# LCD_ControlRev1.net
KiCad netlist of a schematic drawn in EAGLE
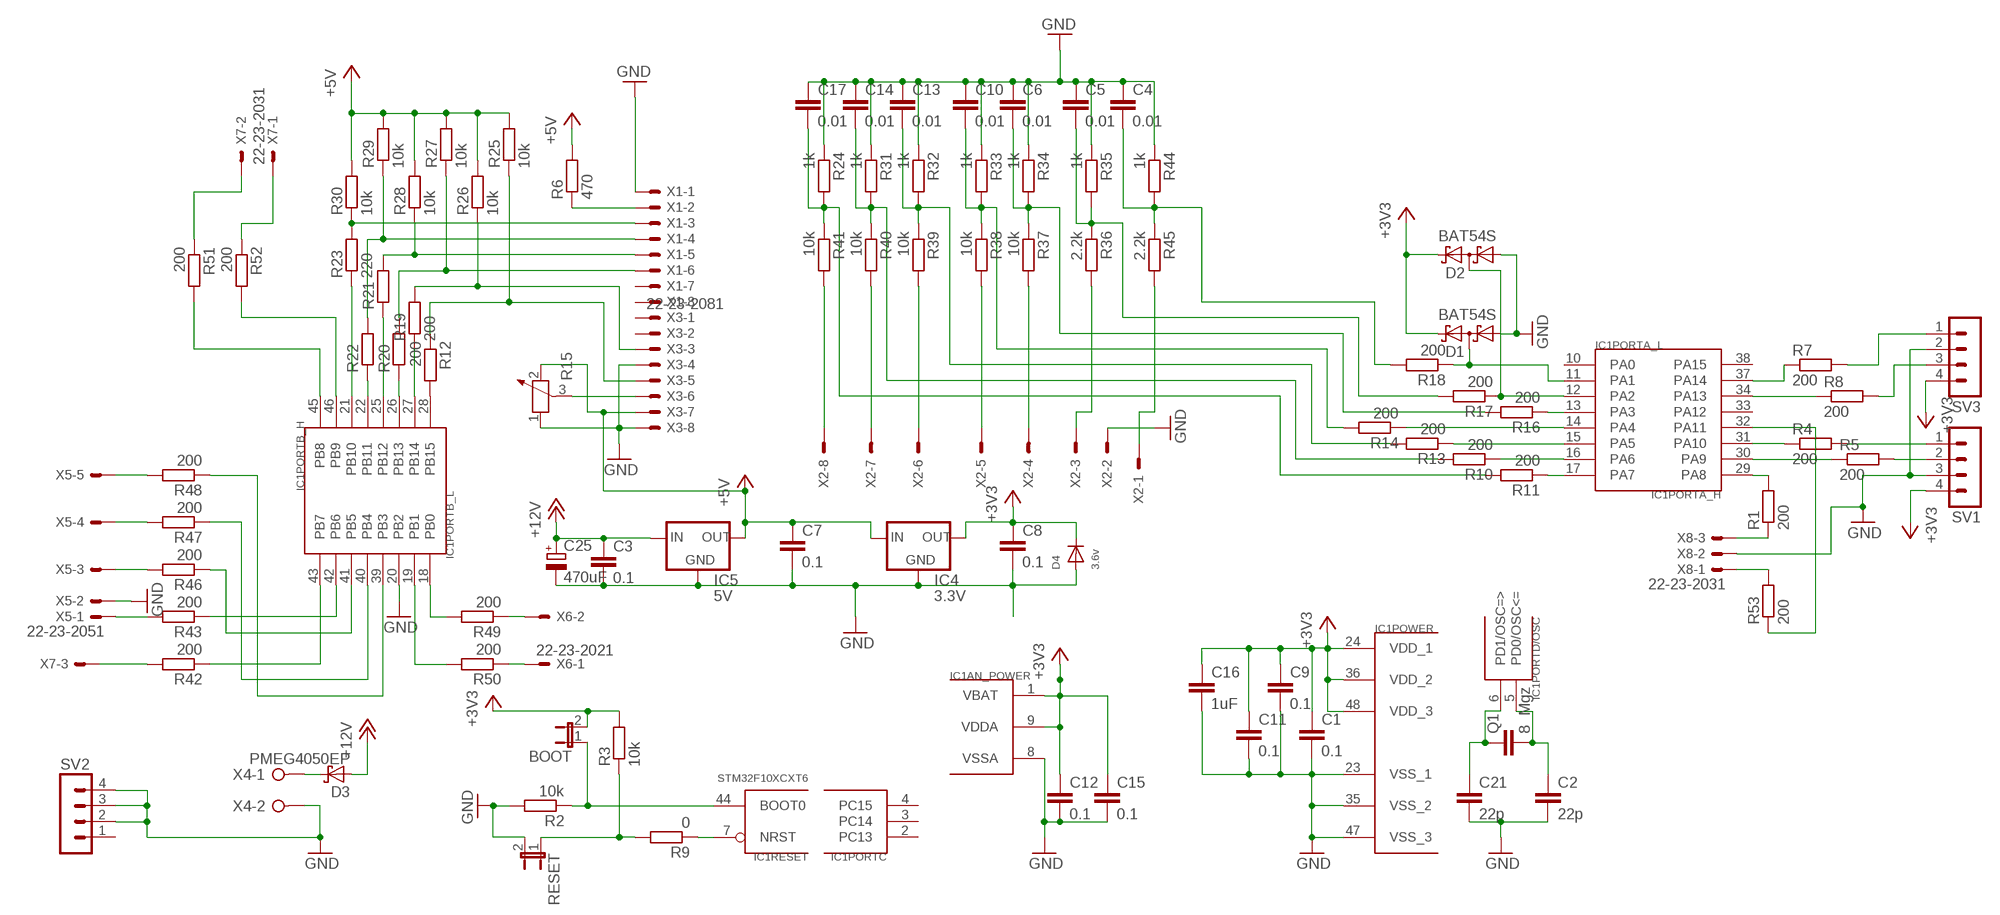
[diagram p0: schematic, sheet 1]

(export (version "E")
  (design (tool "Eeschema 10.0.6"))
  (components
    (comp (ref "BOOT")
      (value "JP1E")
      (footprint "eagle-import:JP1")
      (libsource (lib "eagle-import") (part "JP1E"))
    )
    (comp (ref "C1")
      (value "0.1")
      (footprint "eagle-import:C0402")
      (libsource (lib "eagle-import") (part "C-EUC0402"))
    )
    (comp (ref "C2")
      (value "22p")
      (footprint "eagle-import:C0603")
      (libsource (lib "eagle-import") (part "C-EUC0603"))
    )
    (comp (ref "C3")
      (value "0.1")
      (footprint "eagle-import:C1206")
      (libsource (lib "eagle-import") (part "C-EUC1206"))
    )
    (comp (ref "C4")
      (value "0.01")
      (footprint "eagle-import:C0603")
      (libsource (lib "eagle-import") (part "rcl_334_C-EUC0603"))
    )
    (comp (ref "C5")
      (value "0.01")
      (footprint "eagle-import:C0603")
      (libsource (lib "eagle-import") (part "rcl_334_C-EUC0603"))
    )
    (comp (ref "C6")
      (value "0.01")
      (footprint "eagle-import:C0603")
      (libsource (lib "eagle-import") (part "rcl_334_C-EUC0603"))
    )
    (comp (ref "C7")
      (value "0.1")
      (footprint "eagle-import:C1206")
      (libsource (lib "eagle-import") (part "C-EUC1206"))
    )
    (comp (ref "C8")
      (value "0.1")
      (footprint "eagle-import:C1206")
      (libsource (lib "eagle-import") (part "C-EUC1206"))
    )
    (comp (ref "C9")
      (value "0.1")
      (footprint "eagle-import:C0402")
      (libsource (lib "eagle-import") (part "C-EUC0402"))
    )
    (comp (ref "C10")
      (value "0.01")
      (footprint "eagle-import:C0603")
      (libsource (lib "eagle-import") (part "rcl_334_C-EUC0603"))
    )
    (comp (ref "C11")
      (value "0.1")
      (footprint "eagle-import:C0402")
      (libsource (lib "eagle-import") (part "C-EUC0402"))
    )
    (comp (ref "C12")
      (value "0.1")
      (footprint "eagle-import:C0402")
      (libsource (lib "eagle-import") (part "C-EUC0402"))
    )
    (comp (ref "C13")
      (value "0.01")
      (footprint "eagle-import:C0603")
      (libsource (lib "eagle-import") (part "rcl_334_C-EUC0603"))
    )
    (comp (ref "C14")
      (value "0.01")
      (footprint "eagle-import:C0603")
      (libsource (lib "eagle-import") (part "rcl_334_C-EUC0603"))
    )
    (comp (ref "C15")
      (value "0.1")
      (footprint "eagle-import:C0402")
      (libsource (lib "eagle-import") (part "C-EUC0402"))
    )
    (comp (ref "C16")
      (value "1uF")
      (footprint "eagle-import:C0603")
      (libsource (lib "eagle-import") (part "C-EUC0603"))
    )
    (comp (ref "C17")
      (value "0.01")
      (footprint "eagle-import:C0603")
      (libsource (lib "eagle-import") (part "rcl_334_C-EUC0603"))
    )
    (comp (ref "C21")
      (value "22p")
      (footprint "eagle-import:C0603")
      (libsource (lib "eagle-import") (part "C-EUC0603"))
    )
    (comp (ref "C25")
      (value "470uF")
      (footprint "eagle-import:E5-10,5")
      (libsource (lib "eagle-import") (part "CPOL-EUE5-10.5"))
    )
    (comp (ref "D1")
      (value "BAT54S")
      (footprint "eagle-import:SOT23")
      (libsource (lib "eagle-import") (part "BAT54S"))
    )
    (comp (ref "D2")
      (value "BAT54S")
      (footprint "eagle-import:SOT23")
      (libsource (lib "eagle-import") (part "BAT54S"))
    )
    (comp (ref "D3")
      (value "PMEG4050EP")
      (footprint "eagle-import:SOD128")
      (libsource (lib "eagle-import") (part "PMEG4050EP"))
    )
    (comp (ref "D4")
      (value "3.6v")
      (footprint "eagle-import:SOD-123")
      (libsource (lib "eagle-import") (part "DIODESOD-123"))
    )
    (comp (ref "IC1")
      (value "STM32F10XCXT6")
      (footprint "eagle-import:TQFP48")
      (libsource (lib "eagle-import") (part "STM32F10XCXT6"))
    )
    (comp (ref "IC4")
      (value "3.3V")
      (footprint "eagle-import:SOT223")
      (libsource (lib "eagle-import") (part "LM1117"))
    )
    (comp (ref "IC5")
      (value "5V")
      (footprint "eagle-import:SOT223")
      (libsource (lib "eagle-import") (part "LM1117"))
    )
    (comp (ref "Q1")
      (value "8 Mgz")
      (footprint "eagle-import:C050-024X044")
      (libsource (lib "eagle-import") (part "C-EU050-024X044"))
    )
    (comp (ref "R1")
      (value "200")
      (footprint "eagle-import:R0603")
      (libsource (lib "eagle-import") (part "R-EU_R0603"))
    )
    (comp (ref "R2")
      (value "10k")
      (footprint "eagle-import:R0603")
      (libsource (lib "eagle-import") (part "R-EU_R0603"))
    )
    (comp (ref "R3")
      (value "10k")
      (footprint "eagle-import:M1206")
      (libsource (lib "eagle-import") (part "R-EU_M1206"))
    )
    (comp (ref "R4")
      (value "200")
      (footprint "eagle-import:R0603")
      (libsource (lib "eagle-import") (part "R-EU_R0603"))
    )
    (comp (ref "R5")
      (value "200")
      (footprint "eagle-import:R0603")
      (libsource (lib "eagle-import") (part "R-EU_R0603"))
    )
    (comp (ref "R6")
      (value "470")
      (footprint "eagle-import:R0603")
      (libsource (lib "eagle-import") (part "R-EU_R0603"))
    )
    (comp (ref "R7")
      (value "200")
      (footprint "eagle-import:R0603")
      (libsource (lib "eagle-import") (part "R-EU_R0603"))
    )
    (comp (ref "R8")
      (value "200")
      (footprint "eagle-import:R0603")
      (libsource (lib "eagle-import") (part "R-EU_R0603"))
    )
    (comp (ref "R9")
      (value "0")
      (footprint "eagle-import:M1206")
      (libsource (lib "eagle-import") (part "R-EU_M1206"))
    )
    (comp (ref "R10")
      (value "200")
      (footprint "eagle-import:R0603")
      (libsource (lib "eagle-import") (part "R-EU_R0603"))
    )
    (comp (ref "R11")
      (value "200")
      (footprint "eagle-import:R0603")
      (libsource (lib "eagle-import") (part "R-EU_R0603"))
    )
    (comp (ref "R12")
      (value "200")
      (footprint "eagle-import:M1206")
      (libsource (lib "eagle-import") (part "R-EU_M1206"))
    )
    (comp (ref "R13")
      (value "200")
      (footprint "eagle-import:R0603")
      (libsource (lib "eagle-import") (part "R-EU_R0603"))
    )
    (comp (ref "R14")
      (value "200")
      (footprint "eagle-import:R0603")
      (libsource (lib "eagle-import") (part "R-EU_R0603"))
    )
    (comp (ref "R15")
      (value "POTENTIOMETER_PT-10S")
      (footprint "eagle-import:PT-10S")
      (libsource (lib "eagle-import") (part "POTENTIOMETER_PT-10S"))
    )
    (comp (ref "R16")
      (value "200")
      (footprint "eagle-import:R0603")
      (libsource (lib "eagle-import") (part "R-EU_R0603"))
    )
    (comp (ref "R17")
      (value "200")
      (footprint "eagle-import:R0603")
      (libsource (lib "eagle-import") (part "R-EU_R0603"))
    )
    (comp (ref "R18")
      (value "200")
      (footprint "eagle-import:R0603")
      (libsource (lib "eagle-import") (part "R-EU_R0603"))
    )
    (comp (ref "R19")
      (value "200")
      (footprint "eagle-import:R0603")
      (libsource (lib "eagle-import") (part "R-EU_R0603"))
    )
    (comp (ref "R20")
      (value "R-EU_R0603")
      (footprint "eagle-import:R0603")
      (libsource (lib "eagle-import") (part "R-EU_R0603"))
    )
    (comp (ref "R21")
      (value "R-EU_R0603")
      (footprint "eagle-import:R0603")
      (libsource (lib "eagle-import") (part "R-EU_R0603"))
    )
    (comp (ref "R22")
      (value "R-EU_R0603")
      (footprint "eagle-import:R0603")
      (libsource (lib "eagle-import") (part "R-EU_R0603"))
    )
    (comp (ref "R23")
      (value "220")
      (footprint "eagle-import:R0603")
      (libsource (lib "eagle-import") (part "R-EU_R0603"))
    )
    (comp (ref "R24")
      (value "1k")
      (footprint "eagle-import:R0603")
      (libsource (lib "eagle-import") (part "R-EU_R0603"))
    )
    (comp (ref "R25")
      (value "10k")
      (footprint "eagle-import:R0603")
      (libsource (lib "eagle-import") (part "R-EU_R0603"))
    )
    (comp (ref "R26")
      (value "10k")
      (footprint "eagle-import:R0603")
      (libsource (lib "eagle-import") (part "R-EU_R0603"))
    )
    (comp (ref "R27")
      (value "10k")
      (footprint "eagle-import:R0603")
      (libsource (lib "eagle-import") (part "R-EU_R0603"))
    )
    (comp (ref "R28")
      (value "10k")
      (footprint "eagle-import:R0603")
      (libsource (lib "eagle-import") (part "R-EU_R0603"))
    )
    (comp (ref "R29")
      (value "10k")
      (footprint "eagle-import:R0603")
      (libsource (lib "eagle-import") (part "R-EU_R0603"))
    )
    (comp (ref "R30")
      (value "10k")
      (footprint "eagle-import:R0603")
      (libsource (lib "eagle-import") (part "R-EU_R0603"))
    )
    (comp (ref "R31")
      (value "1k")
      (footprint "eagle-import:R0603")
      (libsource (lib "eagle-import") (part "R-EU_R0603"))
    )
    (comp (ref "R32")
      (value "1k")
      (footprint "eagle-import:R0603")
      (libsource (lib "eagle-import") (part "R-EU_R0603"))
    )
    (comp (ref "R33")
      (value "1k")
      (footprint "eagle-import:R0603")
      (libsource (lib "eagle-import") (part "R-EU_R0603"))
    )
    (comp (ref "R34")
      (value "1k")
      (footprint "eagle-import:R0603")
      (libsource (lib "eagle-import") (part "R-EU_R0603"))
    )
    (comp (ref "R35")
      (value "1k")
      (footprint "eagle-import:R0603")
      (fields (field (name "SPICEPREFIX") "R"))
      (libsource (lib "eagle-import") (part "R-EU_R0603"))
    )
    (comp (ref "R36")
      (value "2.2k")
      (footprint "eagle-import:R0603")
      (libsource (lib "eagle-import") (part "R-EU_R0603"))
    )
    (comp (ref "R37")
      (value "10k")
      (footprint "eagle-import:R0603")
      (libsource (lib "eagle-import") (part "R-EU_R0603"))
    )
    (comp (ref "R38")
      (value "10k")
      (footprint "eagle-import:R0603")
      (libsource (lib "eagle-import") (part "R-EU_R0603"))
    )
    (comp (ref "R39")
      (value "10k")
      (footprint "eagle-import:R0603")
      (libsource (lib "eagle-import") (part "R-EU_R0603"))
    )
    (comp (ref "R40")
      (value "10k")
      (footprint "eagle-import:R0603")
      (libsource (lib "eagle-import") (part "R-EU_R0603"))
    )
    (comp (ref "R41")
      (value "10k")
      (footprint "eagle-import:R0603")
      (libsource (lib "eagle-import") (part "R-EU_R0603"))
    )
    (comp (ref "R42")
      (value "200")
      (footprint "eagle-import:R0603")
      (libsource (lib "eagle-import") (part "R-EU_R0603"))
    )
    (comp (ref "R43")
      (value "200")
      (footprint "eagle-import:R0603")
      (libsource (lib "eagle-import") (part "R-EU_R0603"))
    )
    (comp (ref "R44")
      (value "1k")
      (footprint "eagle-import:R0603")
      (libsource (lib "eagle-import") (part "R-EU_R0603"))
    )
    (comp (ref "R45")
      (value "2.2k")
      (footprint "eagle-import:R0603")
      (libsource (lib "eagle-import") (part "R-EU_R0603"))
    )
    (comp (ref "R46")
      (value "200")
      (footprint "eagle-import:R0603")
      (libsource (lib "eagle-import") (part "R-EU_R0603"))
    )
    (comp (ref "R47")
      (value "200")
      (footprint "eagle-import:R0603")
      (libsource (lib "eagle-import") (part "R-EU_R0603"))
    )
    (comp (ref "R48")
      (value "200")
      (footprint "eagle-import:R0603")
      (libsource (lib "eagle-import") (part "R-EU_R0603"))
    )
    (comp (ref "R49")
      (value "200")
      (footprint "eagle-import:R0603")
      (libsource (lib "eagle-import") (part "R-EU_R0603"))
    )
    (comp (ref "R50")
      (value "200")
      (footprint "eagle-import:R0603")
      (libsource (lib "eagle-import") (part "R-EU_R0603"))
    )
    (comp (ref "R51")
      (value "200")
      (footprint "eagle-import:R0603")
      (libsource (lib "eagle-import") (part "R-EU_R0603"))
    )
    (comp (ref "R52")
      (value "200")
      (footprint "eagle-import:R0603")
      (libsource (lib "eagle-import") (part "R-EU_R0603"))
    )
    (comp (ref "R53")
      (value "200")
      (footprint "eagle-import:R0603")
      (libsource (lib "eagle-import") (part "R-EU_R0603"))
    )
    (comp (ref "RESET")
      (value "JP1E")
      (footprint "eagle-import:JP1")
      (libsource (lib "eagle-import") (part "JP1E"))
    )
    (comp (ref "SV1")
      (value "MA04-1")
      (footprint "eagle-import:MA04-1")
      (libsource (lib "eagle-import") (part "MA04-1"))
    )
    (comp (ref "SV2")
      (value "MA04-1")
      (footprint "eagle-import:MA04-1")
      (libsource (lib "eagle-import") (part "MA04-1"))
    )
    (comp (ref "SV3")
      (value "MA04-1")
      (footprint "eagle-import:MA04-1")
      (libsource (lib "eagle-import") (part "MA04-1"))
    )
    (comp (ref "X1")
      (value "22-23-2081")
      (footprint "eagle-import:22-23-2081")
      (fields (field (name "MF") "MOLEX"))
      (libsource (lib "eagle-import") (part "22-23-2081"))
    )
    (comp (ref "X2")
      (value "22-23-2081")
      (footprint "eagle-import:22-23-2081")
      (fields (field (name "MF") "MOLEX"))
      (libsource (lib "eagle-import") (part "con-molex_165_22-23-2081"))
    )
    (comp (ref "X3")
      (value "22-23-2081")
      (footprint "eagle-import:22-23-2081")
      (fields (field (name "MF") "MOLEX"))
      (libsource (lib "eagle-import") (part "22-23-2081"))
    )
    (comp (ref "X4")
      (value "W237-02P")
      (footprint "eagle-import:W237-132")
      (libsource (lib "eagle-import") (part "W237-02P"))
    )
    (comp (ref "X5")
      (value "22-23-2051")
      (footprint "eagle-import:22-23-2051")
      (fields (field (name "MF") "MOLEX"))
      (libsource (lib "eagle-import") (part "22-23-2051"))
    )
    (comp (ref "X6")
      (value "22-23-2021")
      (footprint "eagle-import:22-23-2021")
      (fields (field (name "MF") "MOLEX"))
      (libsource (lib "eagle-import") (part "22-23-2021"))
    )
    (comp (ref "X7")
      (value "22-23-2031")
      (footprint "eagle-import:22-23-2031")
      (fields (field (name "MF") "MOLEX"))
      (libsource (lib "eagle-import") (part "22-23-2031"))
    )
    (comp (ref "X8")
      (value "22-23-2031")
      (footprint "eagle-import:22-23-2031")
      (fields (field (name "MF") "MOLEX"))
      (libsource (lib "eagle-import") (part "22-23-2031"))
    )
  )
  (nets
    (net (code "1") (name "+3V3") (class "Default")
      (node (ref "BOOT") (pin "2") (pinfunction "2_2") (pintype "passive"))
      (node (ref "C1") (pin "1") (pinfunction "1_1") (pintype "passive"))
      (node (ref "C11") (pin "1") (pinfunction "1_1") (pintype "passive"))
      (node (ref "C12") (pin "1") (pinfunction "1_1") (pintype "passive"))
      (node (ref "C15") (pin "1") (pinfunction "1_1") (pintype "passive"))
      (node (ref "C16") (pin "1") (pinfunction "1_1") (pintype "passive"))
      (node (ref "C8") (pin "1") (pinfunction "1_1") (pintype "passive"))
      (node (ref "C9") (pin "1") (pinfunction "1_1") (pintype "passive"))
      (node (ref "D1") (pin "2") (pinfunction "C2_2") (pintype "passive"))
      (node (ref "D2") (pin "2") (pinfunction "C2_2") (pintype "passive"))
      (node (ref "D4") (pin "C") (pinfunction "C_C") (pintype "passive"))
      (node (ref "IC1") (pin "1") (pinfunction "VBAT_1") (pintype "power_in"))
      (node (ref "IC1") (pin "24") (pinfunction "VDD_1_24") (pintype "power_in"))
      (node (ref "IC1") (pin "36") (pinfunction "VDD_2_36") (pintype "power_in"))
      (node (ref "IC1") (pin "48") (pinfunction "VDD_3_48") (pintype "power_in"))
      (node (ref "IC1") (pin "9") (pinfunction "VDDA_9") (pintype "power_in"))
      (node (ref "IC4") (pin "2") (pinfunction "OUT_2") (pintype "passive"))
      (node (ref "IC4") (pin "4") (pinfunction "OUT_4") (pintype "passive"))
      (node (ref "R3") (pin "2") (pinfunction "2_2") (pintype "passive"))
      (node (ref "SV1") (pin "4") (pinfunction "4_4") (pintype "passive"))
      (node (ref "SV3") (pin "4") (pinfunction "4_4") (pintype "passive"))
    )
    (net (code "2") (name "+5V") (class "Default")
      (node (ref "C7") (pin "1") (pinfunction "1_1") (pintype "passive"))
      (node (ref "IC4") (pin "3") (pinfunction "IN_3") (pintype "input"))
      (node (ref "IC5") (pin "2") (pinfunction "OUT_2") (pintype "passive"))
      (node (ref "IC5") (pin "4") (pinfunction "OUT_4") (pintype "passive"))
      (node (ref "R15") (pin "2") (pinfunction "2_2") (pintype "passive"))
      (node (ref "R25") (pin "2") (pinfunction "2_2") (pintype "passive"))
      (node (ref "R26") (pin "2") (pinfunction "2_2") (pintype "passive"))
      (node (ref "R27") (pin "2") (pinfunction "2_2") (pintype "passive"))
      (node (ref "R28") (pin "2") (pinfunction "2_2") (pintype "passive"))
      (node (ref "R29") (pin "2") (pinfunction "2_2") (pintype "passive"))
      (node (ref "R30") (pin "2") (pinfunction "2_2") (pintype "passive"))
      (node (ref "R6") (pin "2") (pinfunction "2_2") (pintype "passive"))
      (node (ref "X3") (pin "7") (pinfunction "S_7") (pintype "passive"))
    )
    (net (code "3") (name "+12V") (class "Default")
      (node (ref "C25") (pin "+") (pinfunction "+_+") (pintype "passive"))
      (node (ref "C3") (pin "1") (pinfunction "1_1") (pintype "passive"))
      (node (ref "D3") (pin "2") (pinfunction "A_2") (pintype "passive"))
      (node (ref "IC5") (pin "3") (pinfunction "IN_3") (pintype "input"))
    )
    (net (code "4") (name "GND") (class "Default")
      (node (ref "C1") (pin "2") (pinfunction "2_2") (pintype "passive"))
      (node (ref "C10") (pin "1") (pinfunction "1_1") (pintype "passive"))
      (node (ref "C11") (pin "2") (pinfunction "2_2") (pintype "passive"))
      (node (ref "C12") (pin "2") (pinfunction "2_2") (pintype "passive"))
      (node (ref "C13") (pin "1") (pinfunction "1_1") (pintype "passive"))
      (node (ref "C14") (pin "1") (pinfunction "1_1") (pintype "passive"))
      (node (ref "C15") (pin "2") (pinfunction "2_2") (pintype "passive"))
      (node (ref "C16") (pin "2") (pinfunction "2_2") (pintype "passive"))
      (node (ref "C17") (pin "1") (pinfunction "1_1") (pintype "passive"))
      (node (ref "C2") (pin "2") (pinfunction "2_2") (pintype "passive"))
      (node (ref "C21") (pin "2") (pinfunction "2_2") (pintype "passive"))
      (node (ref "C25") (pin "-") (pinfunction "-_-") (pintype "passive"))
      (node (ref "C3") (pin "2") (pinfunction "2_2") (pintype "passive"))
      (node (ref "C4") (pin "1") (pinfunction "1_1") (pintype "passive"))
      (node (ref "C5") (pin "1") (pinfunction "1_1") (pintype "passive"))
      (node (ref "C6") (pin "1") (pinfunction "1_1") (pintype "passive"))
      (node (ref "C7") (pin "2") (pinfunction "2_2") (pintype "passive"))
      (node (ref "C8") (pin "2") (pinfunction "2_2") (pintype "passive"))
      (node (ref "C9") (pin "2") (pinfunction "2_2") (pintype "passive"))
      (node (ref "D1") (pin "1") (pinfunction "A1_1") (pintype "passive"))
      (node (ref "D2") (pin "1") (pinfunction "A1_1") (pintype "passive"))
      (node (ref "D4") (pin "A") (pinfunction "A_A") (pintype "passive"))
      (node (ref "IC1") (pin "20") (pinfunction "PB2_20") (pintype "bidirectional"))
      (node (ref "IC1") (pin "23") (pinfunction "VSS_1_23") (pintype "power_in"))
      (node (ref "IC1") (pin "35") (pinfunction "VSS_2_35") (pintype "power_in"))
      (node (ref "IC1") (pin "47") (pinfunction "VSS_3_47") (pintype "power_in"))
      (node (ref "IC1") (pin "8") (pinfunction "VSSA_8") (pintype "power_in"))
      (node (ref "IC4") (pin "1") (pinfunction "GND_1") (pintype "input"))
      (node (ref "IC5") (pin "1") (pinfunction "GND_1") (pintype "input"))
      (node (ref "R15") (pin "1") (pinfunction "1_1") (pintype "passive"))
      (node (ref "R2") (pin "2") (pinfunction "2_2") (pintype "passive"))
      (node (ref "R24") (pin "1") (pinfunction "1_1") (pintype "passive"))
      (node (ref "R31") (pin "1") (pinfunction "1_1") (pintype "passive"))
      (node (ref "R32") (pin "1") (pinfunction "1_1") (pintype "passive"))
      (node (ref "R33") (pin "1") (pinfunction "1_1") (pintype "passive"))
      (node (ref "R34") (pin "1") (pinfunction "1_1") (pintype "passive"))
      (node (ref "R35") (pin "1") (pinfunction "1_1") (pintype "passive"))
      (node (ref "R44") (pin "1") (pinfunction "1_1") (pintype "passive"))
      (node (ref "RESET") (pin "2") (pinfunction "2_2") (pintype "passive"))
      (node (ref "SV1") (pin "3") (pinfunction "3_3") (pintype "passive"))
      (node (ref "SV2") (pin "2") (pinfunction "2_2") (pintype "passive"))
      (node (ref "SV2") (pin "3") (pinfunction "3_3") (pintype "passive"))
      (node (ref "SV2") (pin "4") (pinfunction "4_4") (pintype "passive"))
      (node (ref "SV3") (pin "2") (pinfunction "2_2") (pintype "passive"))
      (node (ref "X1") (pin "1") (pinfunction "S_1") (pintype "passive"))
      (node (ref "X2") (pin "2") (pinfunction "S_2") (pintype "passive"))
      (node (ref "X3") (pin "4") (pinfunction "S_4") (pintype "passive"))
      (node (ref "X3") (pin "8") (pinfunction "S_8") (pintype "passive"))
      (node (ref "X4") (pin "2") (pinfunction "KL_2") (pintype "passive"))
      (node (ref "X5") (pin "2") (pinfunction "S_2") (pintype "passive"))
      (node (ref "X8") (pin "2") (pinfunction "S_2") (pintype "passive"))
    )
    (net (code "5") (name "Net-(C4-Pad2)") (class "Default")
      (node (ref "C4") (pin "2") (pinfunction "2_2") (pintype "passive"))
      (node (ref "R18") (pin "2") (pinfunction "2_2") (pintype "passive"))
      (node (ref "R44") (pin "2") (pinfunction "2_2") (pintype "passive"))
      (node (ref "R45") (pin "1") (pinfunction "1_1") (pintype "passive"))
    )
    (net (code "6") (name "Net-(C5-Pad2)") (class "Default")
      (node (ref "C5") (pin "2") (pinfunction "2_2") (pintype "passive"))
      (node (ref "R17") (pin "2") (pinfunction "2_2") (pintype "passive"))
      (node (ref "R35") (pin "2") (pinfunction "2_2") (pintype "passive"))
      (node (ref "R36") (pin "1") (pinfunction "1_1") (pintype "passive"))
    )
    (net (code "7") (name "Net-(C6-Pad2)") (class "Default")
      (node (ref "C6") (pin "2") (pinfunction "2_2") (pintype "passive"))
      (node (ref "R16") (pin "2") (pinfunction "2_2") (pintype "passive"))
      (node (ref "R34") (pin "2") (pinfunction "2_2") (pintype "passive"))
      (node (ref "R37") (pin "1") (pinfunction "1_1") (pintype "passive"))
    )
    (net (code "8") (name "Net-(C10-Pad2)") (class "Default")
      (node (ref "C10") (pin "2") (pinfunction "2_2") (pintype "passive"))
      (node (ref "R14") (pin "2") (pinfunction "2_2") (pintype "passive"))
      (node (ref "R33") (pin "2") (pinfunction "2_2") (pintype "passive"))
      (node (ref "R38") (pin "1") (pinfunction "1_1") (pintype "passive"))
    )
    (net (code "9") (name "Net-(C13-Pad2)") (class "Default")
      (node (ref "C13") (pin "2") (pinfunction "2_2") (pintype "passive"))
      (node (ref "R13") (pin "2") (pinfunction "2_2") (pintype "passive"))
      (node (ref "R32") (pin "2") (pinfunction "2_2") (pintype "passive"))
      (node (ref "R39") (pin "1") (pinfunction "1_1") (pintype "passive"))
    )
    (net (code "10") (name "Net-(C14-Pad2)") (class "Default")
      (node (ref "C14") (pin "2") (pinfunction "2_2") (pintype "passive"))
      (node (ref "R10") (pin "2") (pinfunction "2_2") (pintype "passive"))
      (node (ref "R31") (pin "2") (pinfunction "2_2") (pintype "passive"))
      (node (ref "R40") (pin "1") (pinfunction "1_1") (pintype "passive"))
    )
    (net (code "11") (name "Net-(C17-Pad2)") (class "Default")
      (node (ref "C17") (pin "2") (pinfunction "2_2") (pintype "passive"))
      (node (ref "R11") (pin "2") (pinfunction "2_2") (pintype "passive"))
      (node (ref "R24") (pin "2") (pinfunction "2_2") (pintype "passive"))
      (node (ref "R41") (pin "1") (pinfunction "1_1") (pintype "passive"))
    )
    (net (code "12") (name "Net-(D1-C1A2)") (class "Default")
      (node (ref "D1") (pin "3") (pinfunction "C1A2_3") (pintype "passive"))
      (node (ref "IC1") (pin "11") (pinfunction "PA1_11") (pintype "bidirectional"))
      (node (ref "R18") (pin "1") (pinfunction "1_1") (pintype "passive"))
    )
    (net (code "13") (name "Net-(D2-C1A2)") (class "Default")
      (node (ref "D2") (pin "3") (pinfunction "C1A2_3") (pintype "passive"))
      (node (ref "IC1") (pin "12") (pinfunction "PA2_12") (pintype "bidirectional"))
      (node (ref "R17") (pin "1") (pinfunction "1_1") (pintype "passive"))
    )
    (net (code "14") (name "Net-(D3-K)") (class "Default")
      (node (ref "D3") (pin "1") (pinfunction "K_1") (pintype "passive"))
      (node (ref "X4") (pin "1") (pinfunction "KL_1") (pintype "passive"))
    )
    (net (code "15") (name "Net-(IC1B-PA8)") (class "Default")
      (node (ref "IC1") (pin "29") (pinfunction "PA8_29") (pintype "bidirectional"))
      (node (ref "R1") (pin "2") (pinfunction "2_2") (pintype "passive"))
    )
    (net (code "16") (name "Net-(IC1B-PA9)") (class "Default")
      (node (ref "IC1") (pin "30") (pinfunction "PA9_30") (pintype "bidirectional"))
      (node (ref "R5") (pin "1") (pinfunction "1_1") (pintype "passive"))
    )
    (net (code "17") (name "Net-(IC1B-PA10)") (class "Default")
      (node (ref "IC1") (pin "31") (pinfunction "PA10_31") (pintype "bidirectional"))
      (node (ref "R4") (pin "1") (pinfunction "1_1") (pintype "passive"))
    )
    (net (code "18") (name "Net-(IC1B-PA11)") (class "Default")
      (node (ref "IC1") (pin "32") (pinfunction "PA11_32") (pintype "bidirectional"))
      (node (ref "R53") (pin "1") (pinfunction "1_1") (pintype "passive"))
    )
    (net (code "19") (name "Net-(IC1B-PA13)") (class "Default")
      (node (ref "IC1") (pin "34") (pinfunction "PA13_34") (pintype "bidirectional"))
      (node (ref "R8") (pin "1") (pinfunction "1_1") (pintype "passive"))
    )
    (net (code "20") (name "Net-(IC1B-PA14)") (class "Default")
      (node (ref "IC1") (pin "37") (pinfunction "PA14_37") (pintype "bidirectional"))
      (node (ref "R7") (pin "1") (pinfunction "1_1") (pintype "passive"))
    )
    (net (code "21") (name "Net-(IC1C-PA3)") (class "Default")
      (node (ref "IC1") (pin "13") (pinfunction "PA3_13") (pintype "bidirectional"))
      (node (ref "R16") (pin "1") (pinfunction "1_1") (pintype "passive"))
    )
    (net (code "22") (name "Net-(IC1C-PA4)") (class "Default")
      (node (ref "IC1") (pin "14") (pinfunction "PA4_14") (pintype "bidirectional"))
      (node (ref "R14") (pin "1") (pinfunction "1_1") (pintype "passive"))
    )
    (net (code "23") (name "Net-(IC1C-PA5)") (class "Default")
      (node (ref "IC1") (pin "15") (pinfunction "PA5_15") (pintype "bidirectional"))
      (node (ref "R13") (pin "1") (pinfunction "1_1") (pintype "passive"))
    )
    (net (code "24") (name "Net-(IC1C-PA6)") (class "Default")
      (node (ref "IC1") (pin "16") (pinfunction "PA6_16") (pintype "bidirectional"))
      (node (ref "R10") (pin "1") (pinfunction "1_1") (pintype "passive"))
    )
    (net (code "25") (name "Net-(IC1C-PA7)") (class "Default")
      (node (ref "IC1") (pin "17") (pinfunction "PA7_17") (pintype "bidirectional"))
      (node (ref "R11") (pin "1") (pinfunction "1_1") (pintype "passive"))
    )
    (net (code "26") (name "Net-(IC1D-PB8)") (class "Default")
      (node (ref "IC1") (pin "45") (pinfunction "PB8_45") (pintype "bidirectional"))
      (node (ref "R51") (pin "2") (pinfunction "2_2") (pintype "passive"))
    )
    (net (code "27") (name "Net-(IC1D-PB9)") (class "Default")
      (node (ref "IC1") (pin "46") (pinfunction "PB9_46") (pintype "bidirectional"))
      (node (ref "R52") (pin "2") (pinfunction "2_2") (pintype "passive"))
    )
    (net (code "28") (name "Net-(IC1D-PB10)") (class "Default")
      (node (ref "IC1") (pin "21") (pinfunction "PB10_21") (pintype "bidirectional"))
      (node (ref "R23") (pin "1") (pinfunction "1_1") (pintype "passive"))
    )
    (net (code "29") (name "Net-(IC1D-PB11)") (class "Default")
      (node (ref "IC1") (pin "22") (pinfunction "PB11_22") (pintype "bidirectional"))
      (node (ref "R22") (pin "1") (pinfunction "1_1") (pintype "passive"))
    )
    (net (code "30") (name "Net-(IC1D-PB12)") (class "Default")
      (node (ref "IC1") (pin "25") (pinfunction "PB12_25") (pintype "bidirectional"))
      (node (ref "R21") (pin "1") (pinfunction "1_1") (pintype "passive"))
    )
    (net (code "31") (name "Net-(IC1D-PB13)") (class "Default")
      (node (ref "IC1") (pin "26") (pinfunction "PB13_26") (pintype "bidirectional"))
      (node (ref "R20") (pin "1") (pinfunction "1_1") (pintype "passive"))
    )
    (net (code "32") (name "Net-(IC1D-PB14)") (class "Default")
      (node (ref "IC1") (pin "27") (pinfunction "PB14_27") (pintype "bidirectional"))
      (node (ref "R19") (pin "1") (pinfunction "1_1") (pintype "passive"))
    )
    (net (code "33") (name "Net-(IC1D-PB15)") (class "Default")
      (node (ref "IC1") (pin "28") (pinfunction "PB15_28") (pintype "bidirectional"))
      (node (ref "R12") (pin "2") (pinfunction "2_2") (pintype "passive"))
    )
    (net (code "34") (name "Net-(IC1E-PB0)") (class "Default")
      (node (ref "IC1") (pin "18") (pinfunction "PB0_18") (pintype "bidirectional"))
      (node (ref "R49") (pin "2") (pinfunction "2_2") (pintype "passive"))
    )
    (net (code "35") (name "Net-(IC1E-PB1)") (class "Default")
      (node (ref "IC1") (pin "19") (pinfunction "PB1_19") (pintype "bidirectional"))
      (node (ref "R50") (pin "2") (pinfunction "2_2") (pintype "passive"))
    )
    (net (code "36") (name "Net-(IC1E-PB3)") (class "Default")
      (node (ref "IC1") (pin "39") (pinfunction "PB3_39") (pintype "bidirectional"))
      (node (ref "R48") (pin "1") (pinfunction "1_1") (pintype "passive"))
    )
    (net (code "37") (name "Net-(IC1E-PB4)") (class "Default")
      (node (ref "IC1") (pin "40") (pinfunction "PB4_40") (pintype "bidirectional"))
      (node (ref "R47") (pin "1") (pinfunction "1_1") (pintype "passive"))
    )
    (net (code "38") (name "Net-(IC1E-PB5)") (class "Default")
      (node (ref "IC1") (pin "41") (pinfunction "PB5_41") (pintype "bidirectional"))
      (node (ref "R46") (pin "1") (pinfunction "1_1") (pintype "passive"))
    )
    (net (code "39") (name "Net-(IC1E-PB6)") (class "Default")
      (node (ref "IC1") (pin "42") (pinfunction "PB6_42") (pintype "bidirectional"))
      (node (ref "R43") (pin "1") (pinfunction "1_1") (pintype "passive"))
    )
    (net (code "40") (name "Net-(IC1E-PB7)") (class "Default")
      (node (ref "IC1") (pin "43") (pinfunction "PB7_43") (pintype "bidirectional"))
      (node (ref "R42") (pin "1") (pinfunction "1_1") (pintype "passive"))
    )
    (net (code "41") (name "Net-(IC1G-PD0{slash}OSC<=)") (class "Default")
      (node (ref "C2") (pin "1") (pinfunction "1_1") (pintype "passive"))
      (node (ref "IC1") (pin "5") (pinfunction "PD0/OSC<=_5") (pintype "bidirectional"))
      (node (ref "Q1") (pin "2") (pinfunction "2_2") (pintype "passive"))
    )
    (net (code "42") (name "Net-(IC1G-PD1{slash}OSC=>)") (class "Default")
      (node (ref "C21") (pin "1") (pinfunction "1_1") (pintype "passive"))
      (node (ref "IC1") (pin "6") (pinfunction "PD1/OSC=>_6") (pintype "bidirectional"))
      (node (ref "Q1") (pin "1") (pinfunction "1_1") (pintype "passive"))
    )
    (net (code "43") (name "Net-(IC1I-BOOT0)") (class "Default")
      (node (ref "BOOT") (pin "1") (pinfunction "1_1") (pintype "passive"))
      (node (ref "IC1") (pin "44") (pinfunction "BOOT0_44") (pintype "input"))
      (node (ref "R2") (pin "1") (pinfunction "1_1") (pintype "passive"))
    )
    (net (code "44") (name "Net-(IC1I-NRST)") (class "Default")
      (node (ref "IC1") (pin "7") (pinfunction "NRST_7") (pintype "input"))
      (node (ref "R9") (pin "1") (pinfunction "1_1") (pintype "passive"))
    )
    (net (code "45") (name "Net-(R3-Pad1)") (class "Default")
      (node (ref "R3") (pin "1") (pinfunction "1_1") (pintype "passive"))
      (node (ref "R9") (pin "2") (pinfunction "2_2") (pintype "passive"))
      (node (ref "RESET") (pin "1") (pinfunction "1_1") (pintype "passive"))
    )
    (net (code "46") (name "Net-(R4-Pad2)") (class "Default")
      (node (ref "R4") (pin "2") (pinfunction "2_2") (pintype "passive"))
      (node (ref "SV1") (pin "1") (pinfunction "1_1") (pintype "passive"))
    )
    (net (code "47") (name "Net-(R5-Pad2)") (class "Default")
      (node (ref "R5") (pin "2") (pinfunction "2_2") (pintype "passive"))
      (node (ref "SV1") (pin "2") (pinfunction "2_2") (pintype "passive"))
    )
    (net (code "48") (name "Net-(R7-Pad2)") (class "Default")
      (node (ref "R7") (pin "2") (pinfunction "2_2") (pintype "passive"))
      (node (ref "SV3") (pin "1") (pinfunction "1_1") (pintype "passive"))
    )
    (net (code "49") (name "Net-(R8-Pad2)") (class "Default")
      (node (ref "R8") (pin "2") (pinfunction "2_2") (pintype "passive"))
      (node (ref "SV3") (pin "3") (pinfunction "3_3") (pintype "passive"))
    )
    (net (code "50") (name "Net-(X1B-S)") (class "Default")
      (node (ref "R6") (pin "1") (pinfunction "1_1") (pintype "passive"))
      (node (ref "X1") (pin "2") (pinfunction "S_2") (pintype "passive"))
    )
    (net (code "51") (name "Net-(X1C-S)") (class "Default")
      (node (ref "R23") (pin "2") (pinfunction "2_2") (pintype "passive"))
      (node (ref "R30") (pin "1") (pinfunction "1_1") (pintype "passive"))
      (node (ref "X1") (pin "3") (pinfunction "S_3") (pintype "passive"))
    )
    (net (code "52") (name "Net-(X1D-S)") (class "Default")
      (node (ref "R22") (pin "2") (pinfunction "2_2") (pintype "passive"))
      (node (ref "R29") (pin "1") (pinfunction "1_1") (pintype "passive"))
      (node (ref "X1") (pin "4") (pinfunction "S_4") (pintype "passive"))
    )
    (net (code "53") (name "Net-(X1E-S)") (class "Default")
      (node (ref "R21") (pin "2") (pinfunction "2_2") (pintype "passive"))
      (node (ref "R28") (pin "1") (pinfunction "1_1") (pintype "passive"))
      (node (ref "X1") (pin "5") (pinfunction "S_5") (pintype "passive"))
    )
    (net (code "54") (name "Net-(X1F-S)") (class "Default")
      (node (ref "R20") (pin "2") (pinfunction "2_2") (pintype "passive"))
      (node (ref "R27") (pin "1") (pinfunction "1_1") (pintype "passive"))
      (node (ref "X1") (pin "6") (pinfunction "S_6") (pintype "passive"))
    )
    (net (code "55") (name "Net-(X2A-S)") (class "Default")
      (node (ref "R45") (pin "2") (pinfunction "2_2") (pintype "passive"))
      (node (ref "X2") (pin "1") (pinfunction "S_1") (pintype "passive"))
    )
    (net (code "56") (name "Net-(X2C-S)") (class "Default")
      (node (ref "R36") (pin "2") (pinfunction "2_2") (pintype "passive"))
      (node (ref "X2") (pin "3") (pinfunction "S_3") (pintype "passive"))
    )
    (net (code "57") (name "Net-(X2D-S)") (class "Default")
      (node (ref "R37") (pin "2") (pinfunction "2_2") (pintype "passive"))
      (node (ref "X2") (pin "4") (pinfunction "S_4") (pintype "passive"))
    )
    (net (code "58") (name "Net-(X2E-S)") (class "Default")
      (node (ref "R38") (pin "2") (pinfunction "2_2") (pintype "passive"))
      (node (ref "X2") (pin "5") (pinfunction "S_5") (pintype "passive"))
    )
    (net (code "59") (name "Net-(X2F-S)") (class "Default")
      (node (ref "R39") (pin "2") (pinfunction "2_2") (pintype "passive"))
      (node (ref "X2") (pin "6") (pinfunction "S_6") (pintype "passive"))
    )
    (net (code "60") (name "Net-(X2G-S)") (class "Default")
      (node (ref "R40") (pin "2") (pinfunction "2_2") (pintype "passive"))
      (node (ref "X2") (pin "7") (pinfunction "S_7") (pintype "passive"))
    )
    (net (code "61") (name "Net-(X2H-S)") (class "Default")
      (node (ref "R41") (pin "2") (pinfunction "2_2") (pintype "passive"))
      (node (ref "X2") (pin "8") (pinfunction "S_8") (pintype "passive"))
    )
    (net (code "62") (name "Net-(X3C-S)") (class "Default")
      (node (ref "R19") (pin "2") (pinfunction "2_2") (pintype "passive"))
      (node (ref "R26") (pin "1") (pinfunction "1_1") (pintype "passive"))
      (node (ref "X3") (pin "3") (pinfunction "S_3") (pintype "passive"))
    )
    (net (code "63") (name "Net-(X3E-S)") (class "Default")
      (node (ref "R12") (pin "1") (pinfunction "1_1") (pintype "passive"))
      (node (ref "R25") (pin "1") (pinfunction "1_1") (pintype "passive"))
      (node (ref "X3") (pin "5") (pinfunction "S_5") (pintype "passive"))
    )
    (net (code "64") (name "Net-(X3F-S)") (class "Default")
      (node (ref "R15") (pin "3") (pinfunction "3_3") (pintype "passive"))
      (node (ref "X3") (pin "6") (pinfunction "S_6") (pintype "passive"))
    )
    (net (code "65") (name "Net-(X5A-S)") (class "Default")
      (node (ref "R43") (pin "2") (pinfunction "2_2") (pintype "passive"))
      (node (ref "X5") (pin "1") (pinfunction "S_1") (pintype "passive"))
    )
    (net (code "66") (name "Net-(X5C-S)") (class "Default")
      (node (ref "R46") (pin "2") (pinfunction "2_2") (pintype "passive"))
      (node (ref "X5") (pin "3") (pinfunction "S_3") (pintype "passive"))
    )
    (net (code "67") (name "Net-(X5D-S)") (class "Default")
      (node (ref "R47") (pin "2") (pinfunction "2_2") (pintype "passive"))
      (node (ref "X5") (pin "4") (pinfunction "S_4") (pintype "passive"))
    )
    (net (code "68") (name "Net-(X5E-S)") (class "Default")
      (node (ref "R48") (pin "2") (pinfunction "2_2") (pintype "passive"))
      (node (ref "X5") (pin "5") (pinfunction "S_5") (pintype "passive"))
    )
    (net (code "69") (name "Net-(X6A-S)") (class "Default")
      (node (ref "R50") (pin "1") (pinfunction "1_1") (pintype "passive"))
      (node (ref "X6") (pin "1") (pinfunction "S_1") (pintype "passive"))
    )
    (net (code "70") (name "Net-(X6B-S)") (class "Default")
      (node (ref "R49") (pin "1") (pinfunction "1_1") (pintype "passive"))
      (node (ref "X6") (pin "2") (pinfunction "S_2") (pintype "passive"))
    )
    (net (code "71") (name "Net-(X7A-S)") (class "Default")
      (node (ref "R52") (pin "1") (pinfunction "1_1") (pintype "passive"))
      (node (ref "X7") (pin "1") (pinfunction "S_1") (pintype "passive"))
    )
    (net (code "72") (name "Net-(X7B-S)") (class "Default")
      (node (ref "R51") (pin "1") (pinfunction "1_1") (pintype "passive"))
      (node (ref "X7") (pin "2") (pinfunction "S_2") (pintype "passive"))
    )
    (net (code "73") (name "Net-(X7C-S)") (class "Default")
      (node (ref "R42") (pin "2") (pinfunction "2_2") (pintype "passive"))
      (node (ref "X7") (pin "3") (pinfunction "S_3") (pintype "passive"))
    )
    (net (code "74") (name "Net-(X8A-S)") (class "Default")
      (node (ref "R53") (pin "2") (pinfunction "2_2") (pintype "passive"))
      (node (ref "X8") (pin "1") (pinfunction "S_1") (pintype "passive"))
    )
    (net (code "75") (name "Net-(X8C-S)") (class "Default")
      (node (ref "R1") (pin "1") (pinfunction "1_1") (pintype "passive"))
      (node (ref "X8") (pin "3") (pinfunction "S_3") (pintype "passive"))
    )
    (net (code "76") (name "unconnected-(IC1B-PA12-Pad33)") (class "Default")
      (node (ref "IC1") (pin "33") (pinfunction "PA12_33") (pintype "bidirectional"))
    )
    (net (code "77") (name "unconnected-(IC1B-PA15-Pad38)") (class "Default")
      (node (ref "IC1") (pin "38") (pinfunction "PA15_38") (pintype "bidirectional"))
    )
    (net (code "78") (name "unconnected-(IC1C-PA0-Pad10)") (class "Default")
      (node (ref "IC1") (pin "10") (pinfunction "PA0_10") (pintype "bidirectional"))
    )
    (net (code "79") (name "unconnected-(IC1F-PC13-Pad2)") (class "Default")
      (node (ref "IC1") (pin "2") (pinfunction "PC13_2") (pintype "bidirectional"))
    )
    (net (code "80") (name "unconnected-(IC1F-PC14-Pad3)") (class "Default")
      (node (ref "IC1") (pin "3") (pinfunction "PC14_3") (pintype "bidirectional"))
    )
    (net (code "81") (name "unconnected-(IC1F-PC15-Pad4)") (class "Default")
      (node (ref "IC1") (pin "4") (pinfunction "PC15_4") (pintype "bidirectional"))
    )
    (net (code "82") (name "unconnected-(SV2-Pad1)") (class "Default")
      (node (ref "SV2") (pin "1") (pinfunction "1_1") (pintype "passive"))
    )
    (net (code "83") (name "unconnected-(X1G-S-Pad7)") (class "Default")
      (node (ref "X1") (pin "7") (pinfunction "S_7") (pintype "passive"))
    )
    (net (code "84") (name "unconnected-(X1H-S-Pad8)") (class "Default")
      (node (ref "X1") (pin "8") (pinfunction "S_8") (pintype "passive"))
    )
    (net (code "85") (name "unconnected-(X3A-S-Pad1)") (class "Default")
      (node (ref "X3") (pin "1") (pinfunction "S_1") (pintype "passive"))
    )
    (net (code "86") (name "unconnected-(X3B-S-Pad2)") (class "Default")
      (node (ref "X3") (pin "2") (pinfunction "S_2") (pintype "passive"))
    )
  )
)
